# multi_sense32_re1.net
KiCad netlist of a schematic drawn in EAGLE
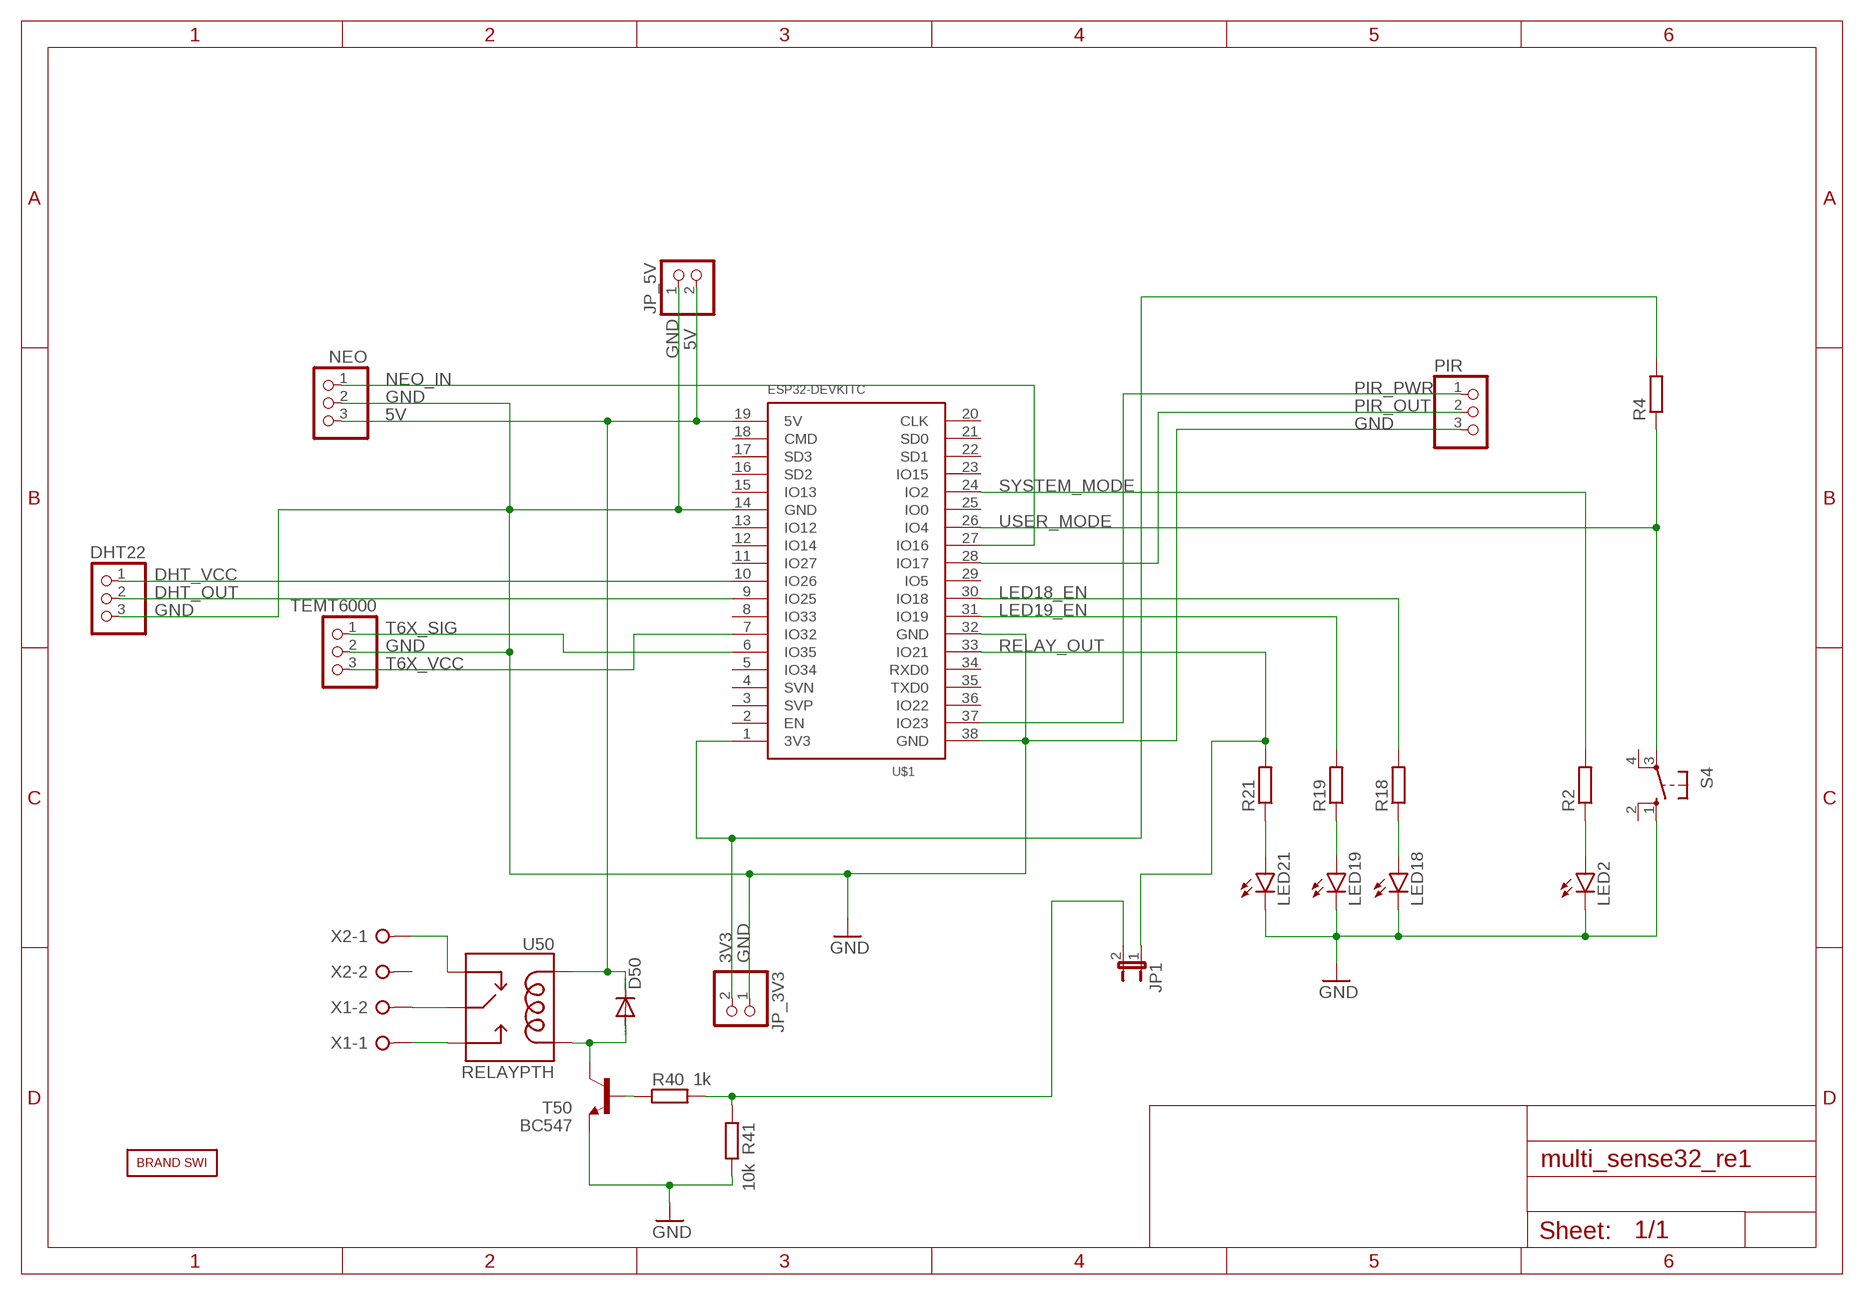
[diagram p0: schematic, sheet 1]

(export (version "E")
  (design (tool "Eeschema 10.0.6"))
  (components
    (comp (ref "D50")
      (value "1N4148DO35-7")
      (footprint "eagle-import:DO35-7")
      (libsource (lib "eagle-import") (part "1N4148DO35-7"))
    )
    (comp (ref "DHT22")
      (value "PINHD-1X3")
      (footprint "eagle-import:1X03")
      (libsource (lib "eagle-import") (part "PINHD-1X3"))
    )
    (comp (ref "JP1")
      (value "JP1E")
      (footprint "eagle-import:JP1")
      (libsource (lib "eagle-import") (part "JP1E"))
    )
    (comp (ref "JP_3V3")
      (value "PINHD-1X2")
      (footprint "eagle-import:1X02")
      (libsource (lib "eagle-import") (part "PINHD-1X2"))
    )
    (comp (ref "JP_5V")
      (value "PINHD-1X2")
      (footprint "eagle-import:1X02")
      (libsource (lib "eagle-import") (part "PINHD-1X2"))
    )
    (comp (ref "LED2")
      (value "LEDCHIPLED_1206")
      (footprint "eagle-import:CHIPLED_1206")
      (libsource (lib "eagle-import") (part "LEDCHIPLED_1206"))
    )
    (comp (ref "LED18")
      (value "LEDCHIPLED_1206")
      (footprint "eagle-import:CHIPLED_1206")
      (libsource (lib "eagle-import") (part "LEDCHIPLED_1206"))
    )
    (comp (ref "LED19")
      (value "LEDCHIPLED_1206")
      (footprint "eagle-import:CHIPLED_1206")
      (libsource (lib "eagle-import") (part "LEDCHIPLED_1206"))
    )
    (comp (ref "LED21")
      (value "LEDCHIPLED_1206")
      (footprint "eagle-import:CHIPLED_1206")
      (libsource (lib "eagle-import") (part "LEDCHIPLED_1206"))
    )
    (comp (ref "NEO")
      (value "PINHD-1X3")
      (footprint "eagle-import:1X03")
      (libsource (lib "eagle-import") (part "PINHD-1X3"))
    )
    (comp (ref "PIR")
      (value "PINHD-1X3")
      (footprint "eagle-import:1X03")
      (libsource (lib "eagle-import") (part "PINHD-1X3"))
    )
    (comp (ref "R2")
      (value "R-EU_R1206")
      (footprint "eagle-import:R1206")
      (libsource (lib "eagle-import") (part "R-EU_R1206"))
    )
    (comp (ref "R4")
      (value "R-EU_R1206")
      (footprint "eagle-import:R1206")
      (libsource (lib "eagle-import") (part "R-EU_R1206"))
    )
    (comp (ref "R18")
      (value "R-EU_R1206")
      (footprint "eagle-import:R1206")
      (libsource (lib "eagle-import") (part "R-EU_R1206"))
    )
    (comp (ref "R19")
      (value "R-EU_R1206")
      (footprint "eagle-import:R1206")
      (libsource (lib "eagle-import") (part "R-EU_R1206"))
    )
    (comp (ref "R21")
      (value "R-EU_R1206")
      (footprint "eagle-import:R1206")
      (libsource (lib "eagle-import") (part "R-EU_R1206"))
    )
    (comp (ref "R40")
      (value "1k")
      (footprint "eagle-import:0207_10")
      (libsource (lib "eagle-import") (part "R-EU_0207/10"))
    )
    (comp (ref "R41")
      (value "10k")
      (footprint "eagle-import:0207_10")
      (libsource (lib "eagle-import") (part "R-EU_0207/10"))
    )
    (comp (ref "S4")
      (value "10-XX")
      (footprint "eagle-import:B3F-10XX")
      (fields (field (name "MPN") "B3F-1000"))
      (libsource (lib "eagle-import") (part "10-XX"))
    )
    (comp (ref "T50")
      (value "BC547")
      (footprint "eagle-import:TO92")
      (libsource (lib "eagle-import") (part "BC547"))
    )
    (comp (ref "TEMT6000")
      (value "PINHD-1X3")
      (footprint "eagle-import:1X03")
      (libsource (lib "eagle-import") (part "PINHD-1X3"))
    )
    (comp (ref "U$1")
      (value "ESP32DEVKITC")
      (footprint "eagle-import:ESP32-DEVKITC")
      (libsource (lib "eagle-import") (part "ESP32DEVKITC"))
    )
    (comp (ref "U$2")
      (value "BRAND_SWI5X7")
      (footprint "eagle-import:BRAND_SWI_5X7")
      (libsource (lib "eagle-import") (part "BRAND_SWI5X7"))
    )
    (comp (ref "U50")
      (value "RELAYPTH")
      (footprint "eagle-import:SRD-05VDC-SL-C")
      (libsource (lib "eagle-import") (part "RELAYPTH"))
    )
    (comp (ref "X1")
      (value "W237-02P")
      (footprint "eagle-import:W237-132")
      (libsource (lib "eagle-import") (part "W237-02P"))
    )
    (comp (ref "X2")
      (value "W237-02P")
      (footprint "eagle-import:W237-132")
      (libsource (lib "eagle-import") (part "W237-02P"))
    )
  )
  (nets
    (net (code "1") (name "/3V3") (class "Default")
      (node (ref "JP_3V3") (pin "2") (pinfunction "2_2") (pintype "passive"))
      (node (ref "R4") (pin "2") (pinfunction "2_2") (pintype "passive"))
      (node (ref "U$1") (pin "1") (pinfunction "3V3_1") (pintype "bidirectional"))
    )
    (net (code "2") (name "/5V") (class "Default")
      (node (ref "D50") (pin "C") (pinfunction "C_C") (pintype "passive"))
      (node (ref "JP_5V") (pin "2") (pinfunction "2_2") (pintype "passive"))
      (node (ref "NEO") (pin "3") (pinfunction "3_3") (pintype "passive"))
      (node (ref "U$1") (pin "19") (pinfunction "5V_19") (pintype "bidirectional"))
      (node (ref "U50") (pin "COIL1") (pinfunction "COIL1_COIL1") (pintype "bidirectional"))
    )
    (net (code "3") (name "/DHT_OUT") (class "Default")
      (node (ref "DHT22") (pin "2") (pinfunction "2_2") (pintype "passive"))
      (node (ref "U$1") (pin "9") (pinfunction "IO25_9") (pintype "bidirectional"))
    )
    (net (code "4") (name "/DHT_VCC") (class "Default")
      (node (ref "DHT22") (pin "1") (pinfunction "1_1") (pintype "passive"))
      (node (ref "U$1") (pin "10") (pinfunction "IO26_10") (pintype "bidirectional"))
    )
    (net (code "5") (name "/LED18_EN") (class "Default")
      (node (ref "R18") (pin "2") (pinfunction "2_2") (pintype "passive"))
      (node (ref "U$1") (pin "30") (pinfunction "IO18_30") (pintype "bidirectional"))
    )
    (net (code "6") (name "/LED19_EN") (class "Default")
      (node (ref "R19") (pin "2") (pinfunction "2_2") (pintype "passive"))
      (node (ref "U$1") (pin "31") (pinfunction "IO19_31") (pintype "bidirectional"))
    )
    (net (code "7") (name "/NEO_IN") (class "Default")
      (node (ref "NEO") (pin "1") (pinfunction "1_1") (pintype "passive"))
      (node (ref "U$1") (pin "27") (pinfunction "IO16_27") (pintype "bidirectional"))
    )
    (net (code "8") (name "/PIR_OUT") (class "Default")
      (node (ref "PIR") (pin "2") (pinfunction "2_2") (pintype "passive"))
      (node (ref "U$1") (pin "28") (pinfunction "IO17_28") (pintype "bidirectional"))
    )
    (net (code "9") (name "/PIR_PWR") (class "Default")
      (node (ref "PIR") (pin "1") (pinfunction "1_1") (pintype "passive"))
      (node (ref "U$1") (pin "37") (pinfunction "IO23_37") (pintype "bidirectional"))
    )
    (net (code "10") (name "/RELAY_OUT") (class "Default")
      (node (ref "JP1") (pin "1") (pinfunction "1_1") (pintype "passive"))
      (node (ref "R21") (pin "2") (pinfunction "2_2") (pintype "passive"))
      (node (ref "U$1") (pin "33") (pinfunction "IO21_33") (pintype "bidirectional"))
    )
    (net (code "11") (name "/SYSTEM_MODE") (class "Default")
      (node (ref "R2") (pin "2") (pinfunction "2_2") (pintype "passive"))
      (node (ref "U$1") (pin "24") (pinfunction "IO2_24") (pintype "bidirectional"))
    )
    (net (code "12") (name "/T6X_SIG") (class "Default")
      (node (ref "TEMT6000") (pin "1") (pinfunction "1_1") (pintype "passive"))
      (node (ref "U$1") (pin "6") (pinfunction "IO35_6") (pintype "bidirectional"))
    )
    (net (code "13") (name "/T6X_VCC") (class "Default")
      (node (ref "TEMT6000") (pin "3") (pinfunction "3_3") (pintype "passive"))
      (node (ref "U$1") (pin "7") (pinfunction "IO32_7") (pintype "bidirectional"))
    )
    (net (code "14") (name "/USER_MODE") (class "Default")
      (node (ref "R4") (pin "1") (pinfunction "1_1") (pintype "passive"))
      (node (ref "S4") (pin "3") (pinfunction "P_3") (pintype "passive"))
      (node (ref "U$1") (pin "26") (pinfunction "IO4_26") (pintype "bidirectional"))
    )
    (net (code "15") (name "GND") (class "Default")
      (node (ref "DHT22") (pin "3") (pinfunction "3_3") (pintype "passive"))
      (node (ref "JP_3V3") (pin "1") (pinfunction "1_1") (pintype "passive"))
      (node (ref "JP_5V") (pin "1") (pinfunction "1_1") (pintype "passive"))
      (node (ref "LED18") (pin "C") (pinfunction "C_C") (pintype "passive"))
      (node (ref "LED19") (pin "C") (pinfunction "C_C") (pintype "passive"))
      (node (ref "LED2") (pin "C") (pinfunction "C_C") (pintype "passive"))
      (node (ref "LED21") (pin "C") (pinfunction "C_C") (pintype "passive"))
      (node (ref "NEO") (pin "2") (pinfunction "2_2") (pintype "passive"))
      (node (ref "PIR") (pin "3") (pinfunction "3_3") (pintype "passive"))
      (node (ref "R41") (pin "2") (pinfunction "2_2") (pintype "passive"))
      (node (ref "S4") (pin "1") (pinfunction "S_1") (pintype "passive"))
      (node (ref "T50") (pin "1") (pinfunction "E_1") (pintype "passive"))
      (node (ref "TEMT6000") (pin "2") (pinfunction "2_2") (pintype "passive"))
      (node (ref "U$1") (pin "14") (pinfunction "GND_14") (pintype "bidirectional"))
      (node (ref "U$1") (pin "32") (pinfunction "GND_32") (pintype "bidirectional"))
      (node (ref "U$1") (pin "38") (pinfunction "GND_38") (pintype "bidirectional"))
    )
    (net (code "16") (name "Net-(JP1-Pad2)") (class "Default")
      (node (ref "JP1") (pin "2") (pinfunction "2_2") (pintype "passive"))
      (node (ref "R40") (pin "2") (pinfunction "2_2") (pintype "passive"))
      (node (ref "R41") (pin "1") (pinfunction "1_1") (pintype "passive"))
    )
    (net (code "17") (name "Net-(LED2-PadA)") (class "Default")
      (node (ref "LED2") (pin "A") (pinfunction "A_A") (pintype "passive"))
      (node (ref "R2") (pin "1") (pinfunction "1_1") (pintype "passive"))
    )
    (net (code "18") (name "Net-(LED18-PadA)") (class "Default")
      (node (ref "LED18") (pin "A") (pinfunction "A_A") (pintype "passive"))
      (node (ref "R18") (pin "1") (pinfunction "1_1") (pintype "passive"))
    )
    (net (code "19") (name "Net-(LED19-PadA)") (class "Default")
      (node (ref "LED19") (pin "A") (pinfunction "A_A") (pintype "passive"))
      (node (ref "R19") (pin "1") (pinfunction "1_1") (pintype "passive"))
    )
    (net (code "20") (name "Net-(LED21-PadA)") (class "Default")
      (node (ref "LED21") (pin "A") (pinfunction "A_A") (pintype "passive"))
      (node (ref "R21") (pin "1") (pinfunction "1_1") (pintype "passive"))
    )
    (net (code "21") (name "Net-(T50-B)") (class "Default")
      (node (ref "R40") (pin "1") (pinfunction "1_1") (pintype "passive"))
      (node (ref "T50") (pin "2") (pinfunction "B_2") (pintype "passive"))
    )
    (net (code "22") (name "Net-(T50-C)") (class "Default")
      (node (ref "D50") (pin "A") (pinfunction "A_A") (pintype "passive"))
      (node (ref "T50") (pin "3") (pinfunction "C_3") (pintype "passive"))
      (node (ref "U50") (pin "COIL0") (pinfunction "COIL0_COIL0") (pintype "bidirectional"))
    )
    (net (code "23") (name "Net-(U50-SWCLOSE)") (class "Default")
      (node (ref "U50") (pin "SWCLOSED") (pinfunction "SWCLOSE_SWCLOSED") (pintype "bidirectional"))
      (node (ref "X2") (pin "1") (pinfunction "KL_1") (pintype "passive"))
    )
    (net (code "24") (name "Net-(X1A-KL)") (class "Default")
      (node (ref "U50") (pin "SWOPEN") (pinfunction "SWOPEN_SWOPEN") (pintype "bidirectional"))
      (node (ref "X1") (pin "1") (pinfunction "KL_1") (pintype "passive"))
    )
    (net (code "25") (name "Net-(X1B-KL)") (class "Default")
      (node (ref "U50") (pin "SWCOMMON") (pinfunction "SWCOMMON_SWCOMMON") (pintype "bidirectional"))
      (node (ref "X1") (pin "2") (pinfunction "KL_2") (pintype "passive"))
    )
    (net (code "26") (name "unconnected-(S4-P1-Pad4)") (class "Default")
      (node (ref "S4") (pin "4") (pinfunction "P1_4") (pintype "passive"))
    )
    (net (code "27") (name "unconnected-(S4-S1-Pad2)") (class "Default")
      (node (ref "S4") (pin "2") (pinfunction "S1_2") (pintype "passive"))
    )
    (net (code "28") (name "unconnected-(U$1-CLK-Pad20)") (class "Default")
      (node (ref "U$1") (pin "20") (pinfunction "CLK_20") (pintype "bidirectional"))
    )
    (net (code "29") (name "unconnected-(U$1-CMD-Pad18)") (class "Default")
      (node (ref "U$1") (pin "18") (pinfunction "CMD_18") (pintype "bidirectional"))
    )
    (net (code "30") (name "unconnected-(U$1-EN-Pad2)") (class "Default")
      (node (ref "U$1") (pin "2") (pinfunction "EN_2") (pintype "bidirectional"))
    )
    (net (code "31") (name "unconnected-(U$1-IO0-Pad25)") (class "Default")
      (node (ref "U$1") (pin "25") (pinfunction "IO0_25") (pintype "bidirectional"))
    )
    (net (code "32") (name "unconnected-(U$1-IO5-Pad29)") (class "Default")
      (node (ref "U$1") (pin "29") (pinfunction "IO5_29") (pintype "bidirectional"))
    )
    (net (code "33") (name "unconnected-(U$1-IO12-Pad13)") (class "Default")
      (node (ref "U$1") (pin "13") (pinfunction "IO12_13") (pintype "bidirectional"))
    )
    (net (code "34") (name "unconnected-(U$1-IO13-Pad15)") (class "Default")
      (node (ref "U$1") (pin "15") (pinfunction "IO13_15") (pintype "bidirectional"))
    )
    (net (code "35") (name "unconnected-(U$1-IO14-Pad12)") (class "Default")
      (node (ref "U$1") (pin "12") (pinfunction "IO14_12") (pintype "bidirectional"))
    )
    (net (code "36") (name "unconnected-(U$1-IO15-Pad23)") (class "Default")
      (node (ref "U$1") (pin "23") (pinfunction "IO15_23") (pintype "bidirectional"))
    )
    (net (code "37") (name "unconnected-(U$1-IO22-Pad36)") (class "Default")
      (node (ref "U$1") (pin "36") (pinfunction "IO22_36") (pintype "bidirectional"))
    )
    (net (code "38") (name "unconnected-(U$1-IO27-Pad11)") (class "Default")
      (node (ref "U$1") (pin "11") (pinfunction "IO27_11") (pintype "bidirectional"))
    )
    (net (code "39") (name "unconnected-(U$1-IO33-Pad8)") (class "Default")
      (node (ref "U$1") (pin "8") (pinfunction "IO33_8") (pintype "bidirectional"))
    )
    (net (code "40") (name "unconnected-(U$1-IO34-Pad5)") (class "Default")
      (node (ref "U$1") (pin "5") (pinfunction "IO34_5") (pintype "bidirectional"))
    )
    (net (code "41") (name "unconnected-(U$1-RXD0-Pad34)") (class "Default")
      (node (ref "U$1") (pin "34") (pinfunction "RXD0_34") (pintype "bidirectional"))
    )
    (net (code "42") (name "unconnected-(U$1-SD0-Pad21)") (class "Default")
      (node (ref "U$1") (pin "21") (pinfunction "SD0_21") (pintype "bidirectional"))
    )
    (net (code "43") (name "unconnected-(U$1-SD1-Pad22)") (class "Default")
      (node (ref "U$1") (pin "22") (pinfunction "SD1_22") (pintype "bidirectional"))
    )
    (net (code "44") (name "unconnected-(U$1-SD2-Pad16)") (class "Default")
      (node (ref "U$1") (pin "16") (pinfunction "SD2_16") (pintype "bidirectional"))
    )
    (net (code "45") (name "unconnected-(U$1-SD3-Pad17)") (class "Default")
      (node (ref "U$1") (pin "17") (pinfunction "SD3_17") (pintype "bidirectional"))
    )
    (net (code "46") (name "unconnected-(U$1-SVN-Pad4)") (class "Default")
      (node (ref "U$1") (pin "4") (pinfunction "SVN_4") (pintype "bidirectional"))
    )
    (net (code "47") (name "unconnected-(U$1-SVP-Pad3)") (class "Default")
      (node (ref "U$1") (pin "3") (pinfunction "SVP_3") (pintype "bidirectional"))
    )
    (net (code "48") (name "unconnected-(U$1-TXD0-Pad35)") (class "Default")
      (node (ref "U$1") (pin "35") (pinfunction "TXD0_35") (pintype "bidirectional"))
    )
    (net (code "49") (name "unconnected-(X2B-KL-Pad2)") (class "Default")
      (node (ref "X2") (pin "2") (pinfunction "KL_2") (pintype "passive"))
    )
  )
)
